# learning_zumo.net
KiCad netlist of a schematic drawn in EAGLE
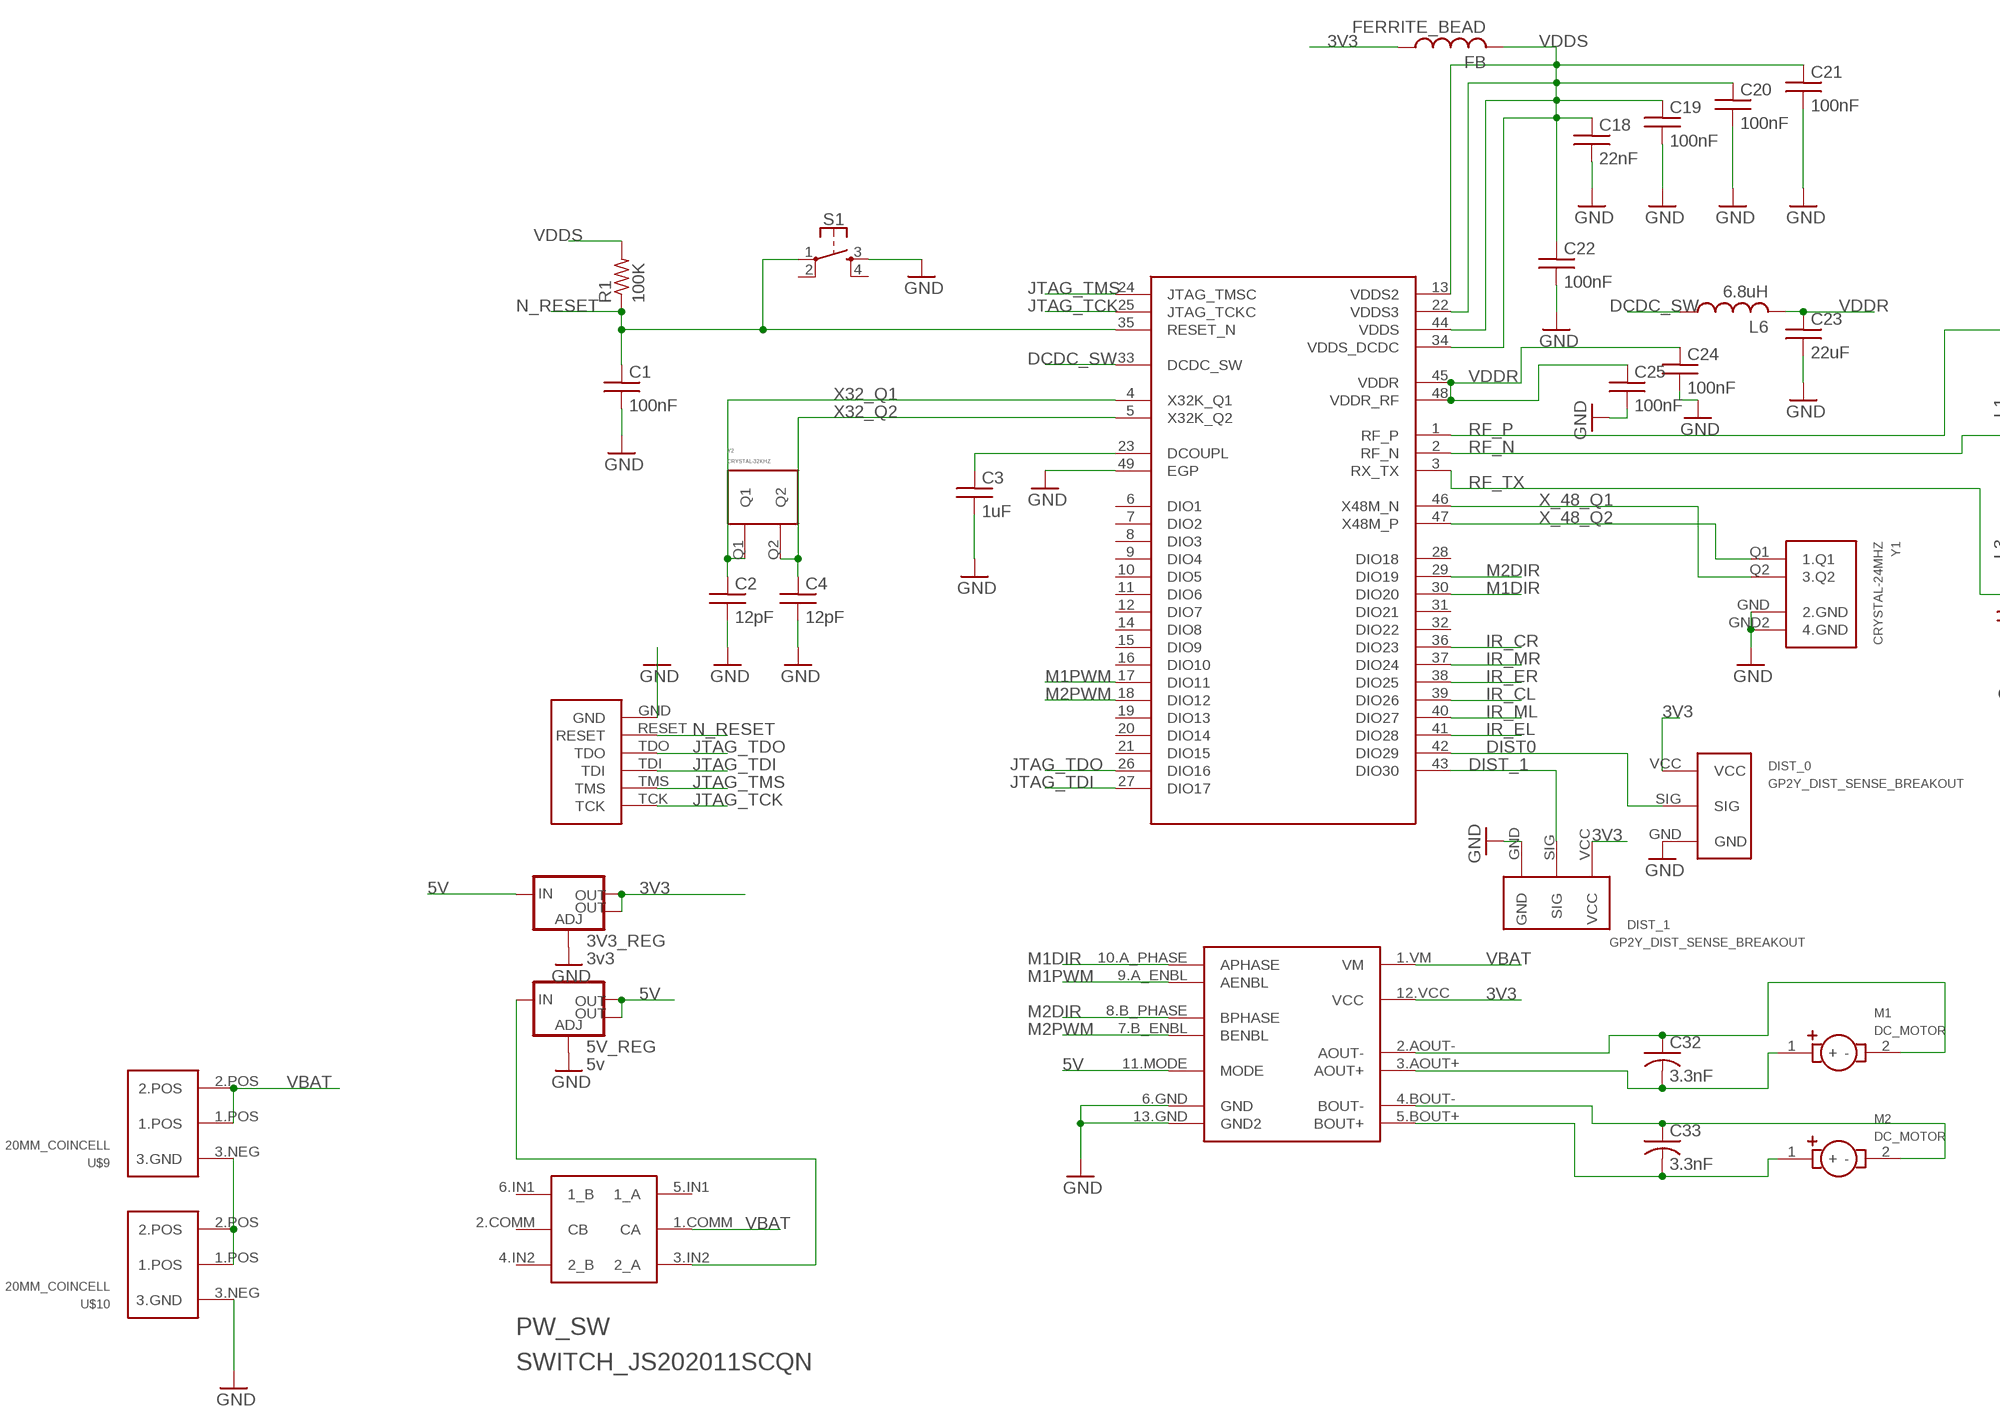
[diagram p0: schematic, sheet 1, part 1 of 2]
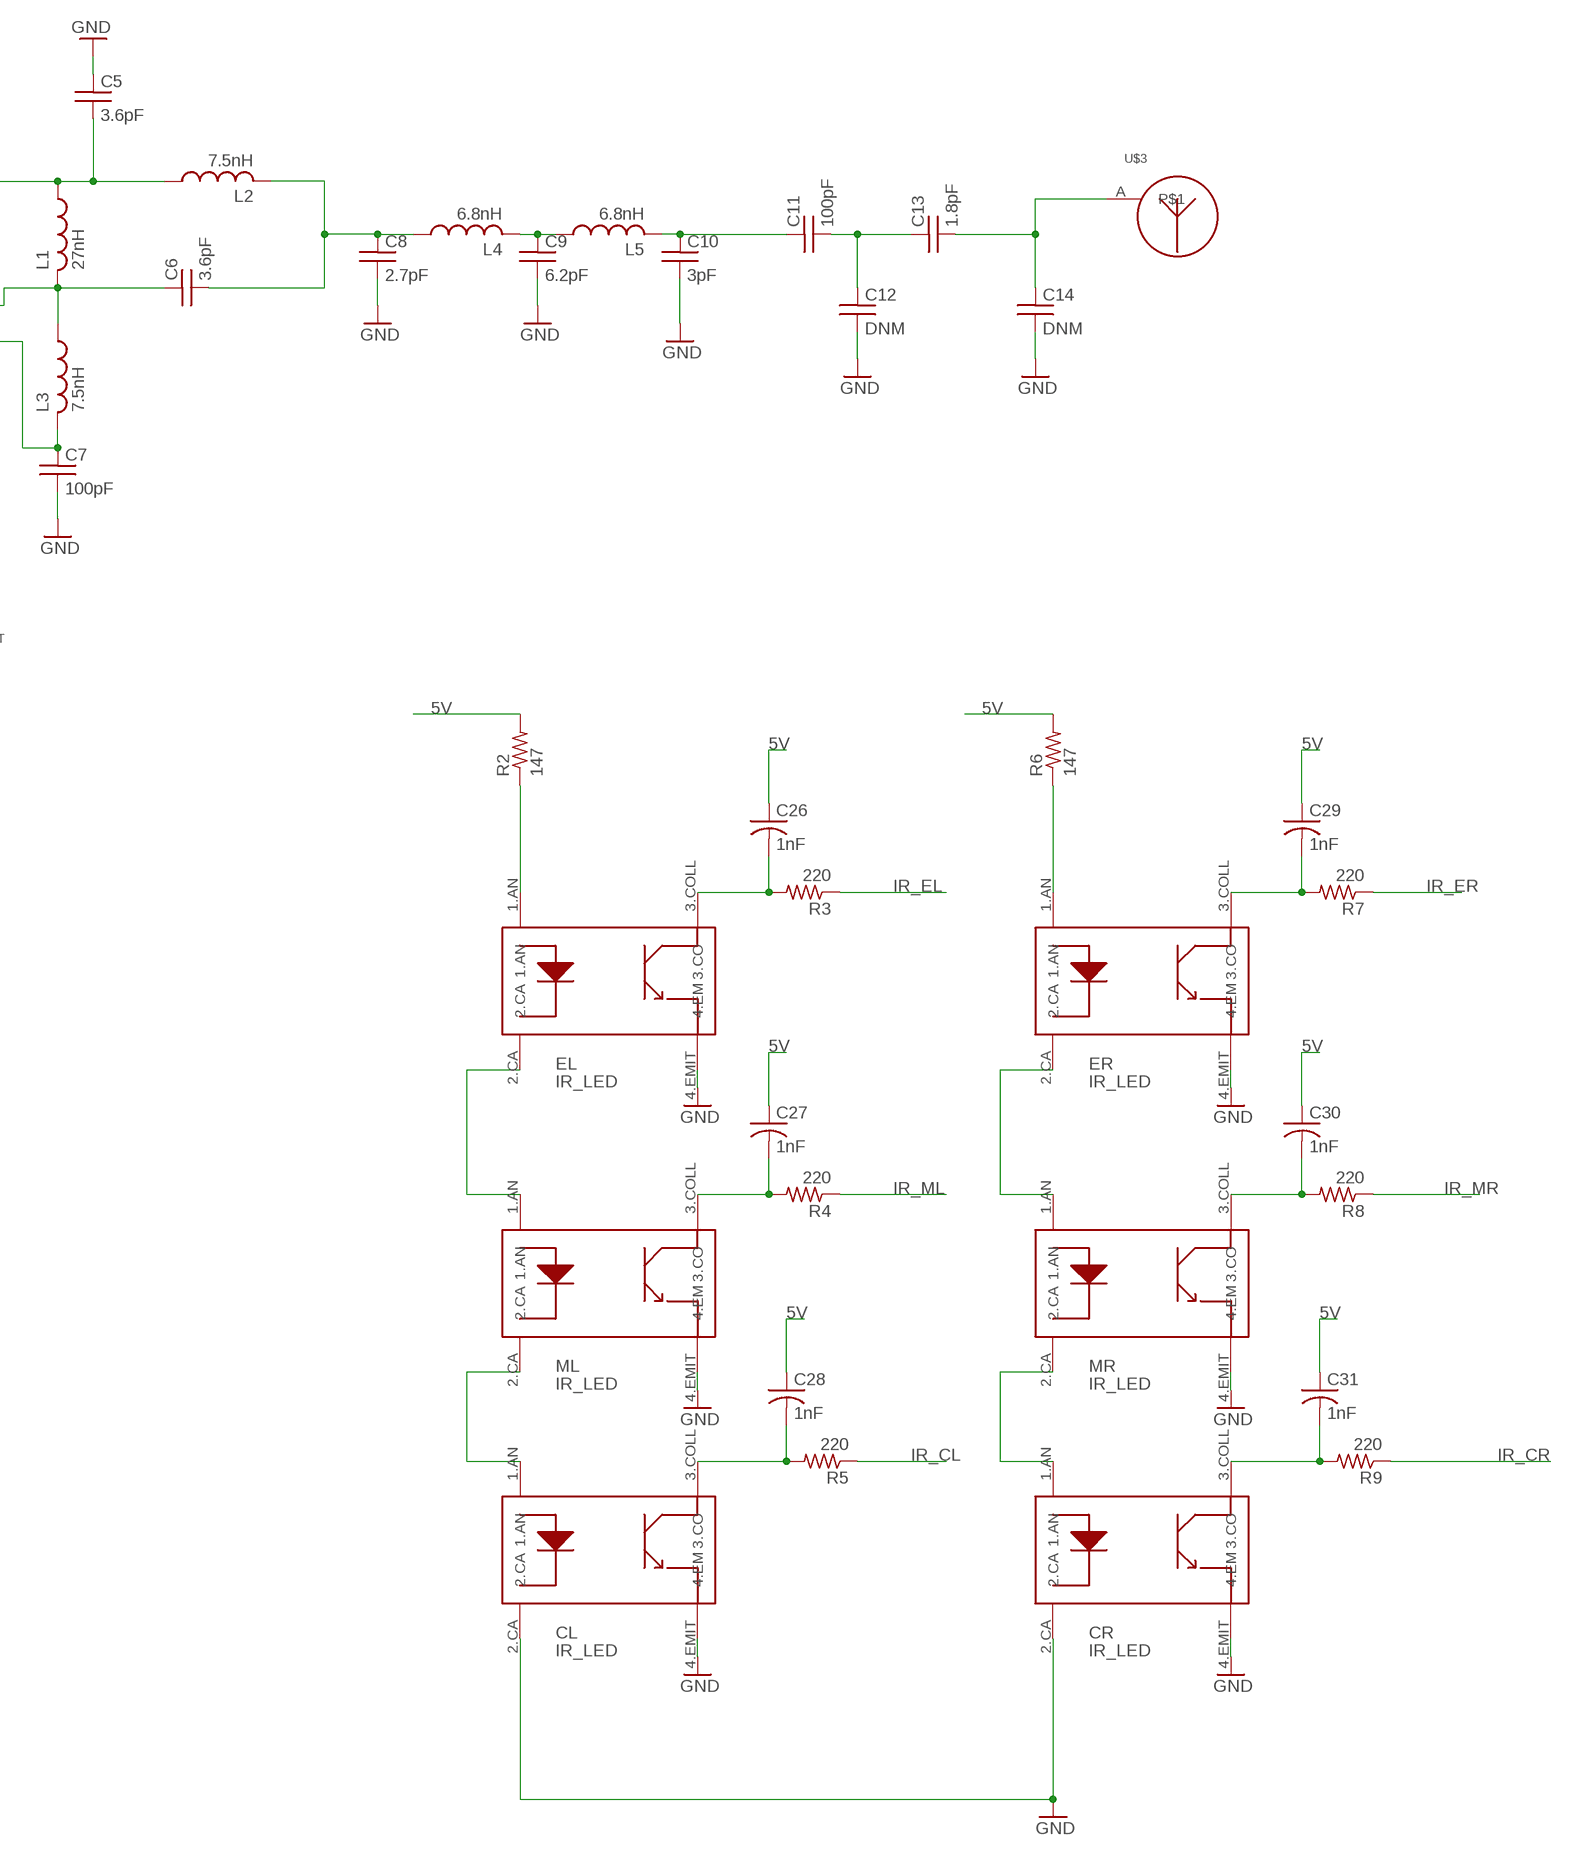
[diagram p1: schematic, sheet 1, part 2 of 2]

(export (version "E")
  (design (tool "Eeschema 10.0.6"))
  (components
    (comp (ref "3V3_REG")
      (value "3v3")
      (footprint "eagle-import:NU32V7_SOT223")
      (libsource (lib "eagle-import") (part "NU32V7_V_REG_LM1117SOT223"))
    )
    (comp (ref "5V_REG")
      (value "5v")
      (footprint "eagle-import:NU32V7_SOT223")
      (libsource (lib "eagle-import") (part "NU32V7_V_REG_LM1117SOT223"))
    )
    (comp (ref "C1")
      (value "100nF")
      (footprint "eagle-import:C0402_US")
      (libsource (lib "eagle-import") (part "C-US"))
    )
    (comp (ref "C2")
      (value "12pF")
      (footprint "eagle-import:C0402_US")
      (libsource (lib "eagle-import") (part "C-US"))
    )
    (comp (ref "C3")
      (value "1uF")
      (footprint "eagle-import:C0402_US")
      (libsource (lib "eagle-import") (part "C-US"))
    )
    (comp (ref "C4")
      (value "12pF")
      (footprint "eagle-import:C0402_US")
      (libsource (lib "eagle-import") (part "C-US"))
    )
    (comp (ref "C5")
      (value "3.6pF")
      (footprint "eagle-import:C0402_US")
      (libsource (lib "eagle-import") (part "C-US"))
    )
    (comp (ref "C6")
      (value "3.6pF")
      (footprint "eagle-import:C0402_US")
      (libsource (lib "eagle-import") (part "C-US"))
    )
    (comp (ref "C7")
      (value "100pF")
      (footprint "eagle-import:C0402_US")
      (libsource (lib "eagle-import") (part "C-US"))
    )
    (comp (ref "C8")
      (value "2.7pF")
      (footprint "eagle-import:C0402_US")
      (libsource (lib "eagle-import") (part "C-US"))
    )
    (comp (ref "C9")
      (value "6.2pF")
      (footprint "eagle-import:C0402_US")
      (libsource (lib "eagle-import") (part "C-US"))
    )
    (comp (ref "C10")
      (value "3pF")
      (footprint "eagle-import:C0402_US")
      (libsource (lib "eagle-import") (part "C-US"))
    )
    (comp (ref "C11")
      (value "100pF")
      (footprint "eagle-import:C0402_US")
      (libsource (lib "eagle-import") (part "C-US"))
    )
    (comp (ref "C12")
      (value "DNM")
      (footprint "eagle-import:C0402_US")
      (libsource (lib "eagle-import") (part "C-US"))
    )
    (comp (ref "C13")
      (value "1.8pF")
      (footprint "eagle-import:C0402_US")
      (libsource (lib "eagle-import") (part "C-US"))
    )
    (comp (ref "C14")
      (value "DNM")
      (footprint "eagle-import:C0402_US")
      (libsource (lib "eagle-import") (part "C-US"))
    )
    (comp (ref "C18")
      (value "22nF")
      (footprint "eagle-import:C0402_US")
      (libsource (lib "eagle-import") (part "C-US"))
    )
    (comp (ref "C19")
      (value "100nF")
      (footprint "eagle-import:C0402_US")
      (libsource (lib "eagle-import") (part "C-US"))
    )
    (comp (ref "C20")
      (value "100nF")
      (footprint "eagle-import:C0402_US")
      (libsource (lib "eagle-import") (part "C-US"))
    )
    (comp (ref "C21")
      (value "100nF")
      (footprint "eagle-import:C0402_US")
      (libsource (lib "eagle-import") (part "C-US"))
    )
    (comp (ref "C22")
      (value "100nF")
      (footprint "eagle-import:C0402_US")
      (libsource (lib "eagle-import") (part "C-US"))
    )
    (comp (ref "C23")
      (value "22uF")
      (footprint "eagle-import:C0402_US")
      (libsource (lib "eagle-import") (part "C-US"))
    )
    (comp (ref "C24")
      (value "100nF")
      (footprint "eagle-import:C0402_US")
      (libsource (lib "eagle-import") (part "C-US"))
    )
    (comp (ref "C25")
      (value "100nF")
      (footprint "eagle-import:C0402_US")
      (libsource (lib "eagle-import") (part "C-US"))
    )
    (comp (ref "C26")
      (value "1nF")
      (footprint "eagle-import:C0805")
      (libsource (lib "eagle-import") (part "C-USC0805"))
    )
    (comp (ref "C27")
      (value "1nF")
      (footprint "eagle-import:C0805")
      (libsource (lib "eagle-import") (part "C-USC0805"))
    )
    (comp (ref "C28")
      (value "1nF")
      (footprint "eagle-import:C0805")
      (libsource (lib "eagle-import") (part "C-USC0805"))
    )
    (comp (ref "C29")
      (value "1nF")
      (footprint "eagle-import:C0805")
      (libsource (lib "eagle-import") (part "C-USC0805"))
    )
    (comp (ref "C30")
      (value "1nF")
      (footprint "eagle-import:C0805")
      (libsource (lib "eagle-import") (part "C-USC0805"))
    )
    (comp (ref "C31")
      (value "1nF")
      (footprint "eagle-import:C0805")
      (libsource (lib "eagle-import") (part "C-USC0805"))
    )
    (comp (ref "C32")
      (value "3.3nF")
      (footprint "eagle-import:C0805")
      (libsource (lib "eagle-import") (part "C-USC0805"))
    )
    (comp (ref "C33")
      (value "3.3nF")
      (footprint "eagle-import:C0805")
      (libsource (lib "eagle-import") (part "C-USC0805"))
    )
    (comp (ref "CL")
      (value "IR_LED")
      (footprint "eagle-import:IR_LED")
      (libsource (lib "eagle-import") (part "IR_LED"))
    )
    (comp (ref "CR")
      (value "IR_LED")
      (footprint "eagle-import:IR_LED")
      (libsource (lib "eagle-import") (part "IR_LED"))
    )
    (comp (ref "DEBUG_HEADER")
      (value "DEBUG_BREAKOUT")
      (footprint "eagle-import:DEBUG_BREAKOUT")
      (libsource (lib "eagle-import") (part "DEBUG_BREAKOUT"))
    )
    (comp (ref "DIST_0")
      (value "GP2Y_DIST_SENSE_BREAKOUT")
      (footprint "eagle-import:1X03")
      (libsource (lib "eagle-import") (part "GP2Y_DIST_SENSE_BREAKOUT"))
    )
    (comp (ref "DIST_1")
      (value "GP2Y_DIST_SENSE_BREAKOUT")
      (footprint "eagle-import:1X03")
      (libsource (lib "eagle-import") (part "GP2Y_DIST_SENSE_BREAKOUT"))
    )
    (comp (ref "DRV8835")
      (value "DRV8835DRV8835")
      (footprint "eagle-import:DRV8835")
      (libsource (lib "eagle-import") (part "DRV8835DRV8835"))
    )
    (comp (ref "EL")
      (value "IR_LED")
      (footprint "eagle-import:IR_LED")
      (libsource (lib "eagle-import") (part "IR_LED"))
    )
    (comp (ref "ER")
      (value "IR_LED")
      (footprint "eagle-import:IR_LED")
      (libsource (lib "eagle-import") (part "IR_LED"))
    )
    (comp (ref "FB")
      (value "FERRITE_BEAD")
      (footprint "eagle-import:FERRITE_BEAD")
      (libsource (lib "eagle-import") (part "FERRITE_BEAD"))
    )
    (comp (ref "L1")
      (value "27nH")
      (footprint "eagle-import:L0402_US")
      (libsource (lib "eagle-import") (part "L-US"))
    )
    (comp (ref "L2")
      (value "7.5nH")
      (footprint "eagle-import:L0402_US")
      (libsource (lib "eagle-import") (part "L-US"))
    )
    (comp (ref "L3")
      (value "7.5nH")
      (footprint "eagle-import:L0402_US")
      (libsource (lib "eagle-import") (part "L-US"))
    )
    (comp (ref "L4")
      (value "6.8nH")
      (footprint "eagle-import:L0402_US")
      (libsource (lib "eagle-import") (part "L-US"))
    )
    (comp (ref "L5")
      (value "6.8nH")
      (footprint "eagle-import:L0402_US")
      (libsource (lib "eagle-import") (part "L-US"))
    )
    (comp (ref "L6")
      (value "6.8uH")
      (footprint "eagle-import:R0805")
      (libsource (lib "eagle-import") (part "L-USL0805"))
    )
    (comp (ref "M1")
      (value "DC_MOTOR")
      (footprint "eagle-import:1X02")
      (libsource (lib "eagle-import") (part "DC_MOTOR"))
    )
    (comp (ref "M2")
      (value "DC_MOTOR")
      (footprint "eagle-import:1X02")
      (libsource (lib "eagle-import") (part "DC_MOTOR"))
    )
    (comp (ref "ML")
      (value "IR_LED")
      (footprint "eagle-import:IR_LED")
      (libsource (lib "eagle-import") (part "IR_LED"))
    )
    (comp (ref "MR")
      (value "IR_LED")
      (footprint "eagle-import:IR_LED")
      (libsource (lib "eagle-import") (part "IR_LED"))
    )
    (comp (ref "PW_SW")
      (value "SWITCH_JS202011SCQN")
      (footprint "eagle-import:SWITCH_JS202011SCQN")
      (libsource (lib "eagle-import") (part "SWITCH_JS202011SCQN"))
    )
    (comp (ref "R1")
      (value "100K")
      (footprint "eagle-import:R0402_US")
      (libsource (lib "eagle-import") (part "R-US{dblquote}"))
    )
    (comp (ref "R2")
      (value "147")
      (footprint "eagle-import:R0805")
      (libsource (lib "eagle-import") (part "R-US_R0805"))
    )
    (comp (ref "R3")
      (value "220")
      (footprint "eagle-import:R0805")
      (libsource (lib "eagle-import") (part "R-US_R0805"))
    )
    (comp (ref "R4")
      (value "220")
      (footprint "eagle-import:R0805")
      (libsource (lib "eagle-import") (part "R-US_R0805"))
    )
    (comp (ref "R5")
      (value "220")
      (footprint "eagle-import:R0805")
      (libsource (lib "eagle-import") (part "R-US_R0805"))
    )
    (comp (ref "R6")
      (value "147")
      (footprint "eagle-import:R0805")
      (libsource (lib "eagle-import") (part "R-US_R0805"))
    )
    (comp (ref "R7")
      (value "220")
      (footprint "eagle-import:R0805")
      (libsource (lib "eagle-import") (part "R-US_R0805"))
    )
    (comp (ref "R8")
      (value "220")
      (footprint "eagle-import:R0805")
      (libsource (lib "eagle-import") (part "R-US_R0805"))
    )
    (comp (ref "R9")
      (value "220")
      (footprint "eagle-import:R0805")
      (libsource (lib "eagle-import") (part "R-US_R0805"))
    )
    (comp (ref "S1")
      (value "MOMENTARY-SWITCH-SPST-2-SMD-4.6X2.8MM")
      (footprint "eagle-import:TACTILE_SWITCH_SMD_4.6X2.8MM")
      (libsource (lib "eagle-import") (part "MOMENTARY-SWITCH-SPST-2-SMD-4.6X2.8MM"))
    )
    (comp (ref "U$1")
      (value "CC1310")
      (footprint "eagle-import:QFN50P700X700X100-49N")
      (libsource (lib "eagle-import") (part "CC1310"))
    )
    (comp (ref "U$3")
      (value "ANTENNA")
      (footprint "eagle-import:ANTENNA")
      (libsource (lib "eagle-import") (part "ANTENNA"))
    )
    (comp (ref "U$9")
      (value "20MM_COINCELL")
      (footprint "eagle-import:20MM_COINCELL")
      (libsource (lib "eagle-import") (part "20MM_COINCELL"))
    )
    (comp (ref "U$10")
      (value "20MM_COINCELL")
      (footprint "eagle-import:20MM_COINCELL")
      (libsource (lib "eagle-import") (part "20MM_COINCELL"))
    )
    (comp (ref "Y1")
      (value "CRYSTAL-24MHZ")
      (footprint "eagle-import:CRYSTAL-24MHZ")
      (libsource (lib "eagle-import") (part "CRYSTAL-24MHZ"))
    )
    (comp (ref "Y2")
      (value "CRYSTAL-32KHZ")
      (footprint "eagle-import:CRYSTAL-32KHZ")
      (libsource (lib "eagle-import") (part "CRYSTAL-32KHZ"))
    )
  )
  (nets
    (net (code "1") (name "/3V3") (class "Default")
      (node (ref "3V3_REG") (pin "OUTPUT") (pinfunction "OUT_OUTPUT") (pintype "output"))
      (node (ref "3V3_REG") (pin "VOUT") (pinfunction "OUT_VOUT") (pintype "output"))
      (node (ref "DIST_0") (pin "VCC") (pinfunction "VCC_VCC") (pintype "bidirectional"))
      (node (ref "DIST_1") (pin "VCC") (pinfunction "VCC_VCC") (pintype "bidirectional"))
      (node (ref "DRV8835") (pin "12.VCC") (pinfunction "VCC_12.VCC") (pintype "bidirectional"))
      (node (ref "FB") (pin "P$1") (pinfunction "1_P$1") (pintype "passive"))
    )
    (net (code "2") (name "/5V") (class "Default")
      (node (ref "3V3_REG") (pin "INPUT") (pinfunction "IN_INPUT") (pintype "input"))
      (node (ref "5V_REG") (pin "OUTPUT") (pinfunction "OUT_OUTPUT") (pintype "output"))
      (node (ref "5V_REG") (pin "VOUT") (pinfunction "OUT_VOUT") (pintype "output"))
      (node (ref "C26") (pin "1") (pinfunction "1_1") (pintype "passive"))
      (node (ref "C27") (pin "1") (pinfunction "1_1") (pintype "passive"))
      (node (ref "C28") (pin "1") (pinfunction "1_1") (pintype "passive"))
      (node (ref "C29") (pin "1") (pinfunction "1_1") (pintype "passive"))
      (node (ref "C30") (pin "1") (pinfunction "1_1") (pintype "passive"))
      (node (ref "C31") (pin "1") (pinfunction "1_1") (pintype "passive"))
      (node (ref "DRV8835") (pin "11.MODE") (pinfunction "MODE_11.MODE") (pintype "bidirectional"))
      (node (ref "R2") (pin "2") (pinfunction "2_2") (pintype "passive"))
      (node (ref "R6") (pin "2") (pinfunction "2_2") (pintype "passive"))
    )
    (net (code "3") (name "/DCDC_SW") (class "Default")
      (node (ref "L6") (pin "1") (pinfunction "1_1") (pintype "passive"))
      (node (ref "U$1") (pin "33") (pinfunction "DCDC_SW_33") (pintype "bidirectional"))
    )
    (net (code "4") (name "/DIST0") (class "Default")
      (node (ref "DIST_0") (pin "SIG") (pinfunction "SIG_SIG") (pintype "bidirectional"))
      (node (ref "U$1") (pin "42") (pinfunction "DIO29_42") (pintype "bidirectional"))
    )
    (net (code "5") (name "/DIST_1") (class "Default")
      (node (ref "DIST_1") (pin "SIG") (pinfunction "SIG_SIG") (pintype "bidirectional"))
      (node (ref "U$1") (pin "43") (pinfunction "DIO30_43") (pintype "bidirectional"))
    )
    (net (code "6") (name "/IR_CL") (class "Default")
      (node (ref "R5") (pin "1") (pinfunction "1_1") (pintype "passive"))
      (node (ref "U$1") (pin "39") (pinfunction "DIO26_39") (pintype "bidirectional"))
    )
    (net (code "7") (name "/IR_CR") (class "Default")
      (node (ref "R9") (pin "1") (pinfunction "1_1") (pintype "passive"))
      (node (ref "U$1") (pin "36") (pinfunction "DIO23_36") (pintype "bidirectional"))
    )
    (net (code "8") (name "/IR_EL") (class "Default")
      (node (ref "R3") (pin "1") (pinfunction "1_1") (pintype "passive"))
      (node (ref "U$1") (pin "41") (pinfunction "DIO28_41") (pintype "bidirectional"))
    )
    (net (code "9") (name "/IR_ER") (class "Default")
      (node (ref "R7") (pin "1") (pinfunction "1_1") (pintype "passive"))
      (node (ref "U$1") (pin "38") (pinfunction "DIO25_38") (pintype "bidirectional"))
    )
    (net (code "10") (name "/IR_ML") (class "Default")
      (node (ref "R4") (pin "1") (pinfunction "1_1") (pintype "passive"))
      (node (ref "U$1") (pin "40") (pinfunction "DIO27_40") (pintype "bidirectional"))
    )
    (net (code "11") (name "/IR_MR") (class "Default")
      (node (ref "R8") (pin "1") (pinfunction "1_1") (pintype "passive"))
      (node (ref "U$1") (pin "37") (pinfunction "DIO24_37") (pintype "bidirectional"))
    )
    (net (code "12") (name "/JTAG_TCK") (class "Default")
      (node (ref "DEBUG_HEADER") (pin "TCK") (pinfunction "TCK_TCK") (pintype "bidirectional"))
      (node (ref "U$1") (pin "25") (pinfunction "JTAG_TCKC_25") (pintype "bidirectional"))
    )
    (net (code "13") (name "/JTAG_TDI") (class "Default")
      (node (ref "DEBUG_HEADER") (pin "TDI") (pinfunction "TDI_TDI") (pintype "bidirectional"))
      (node (ref "U$1") (pin "27") (pinfunction "DIO17_27") (pintype "bidirectional"))
    )
    (net (code "14") (name "/JTAG_TDO") (class "Default")
      (node (ref "DEBUG_HEADER") (pin "TDO") (pinfunction "TDO_TDO") (pintype "bidirectional"))
      (node (ref "U$1") (pin "26") (pinfunction "DIO16_26") (pintype "bidirectional"))
    )
    (net (code "15") (name "/JTAG_TMS") (class "Default")
      (node (ref "DEBUG_HEADER") (pin "TMS") (pinfunction "TMS_TMS") (pintype "bidirectional"))
      (node (ref "U$1") (pin "24") (pinfunction "JTAG_TMSC_24") (pintype "bidirectional"))
    )
    (net (code "16") (name "/M1DIR") (class "Default")
      (node (ref "DRV8835") (pin "10.A_PHASE") (pinfunction "APHASE_10.A_PHASE") (pintype "bidirectional"))
      (node (ref "U$1") (pin "30") (pinfunction "DIO20_30") (pintype "bidirectional"))
    )
    (net (code "17") (name "/M1PWM") (class "Default")
      (node (ref "DRV8835") (pin "9.A_ENBL") (pinfunction "AENBL_9.A_ENBL") (pintype "bidirectional"))
      (node (ref "U$1") (pin "17") (pinfunction "DIO11_17") (pintype "bidirectional"))
    )
    (net (code "18") (name "/M2DIR") (class "Default")
      (node (ref "DRV8835") (pin "8.B_PHASE") (pinfunction "BPHASE_8.B_PHASE") (pintype "bidirectional"))
      (node (ref "U$1") (pin "29") (pinfunction "DIO19_29") (pintype "bidirectional"))
    )
    (net (code "19") (name "/M2PWM") (class "Default")
      (node (ref "DRV8835") (pin "7.B_ENBL") (pinfunction "BENBL_7.B_ENBL") (pintype "bidirectional"))
      (node (ref "U$1") (pin "18") (pinfunction "DIO12_18") (pintype "bidirectional"))
    )
    (net (code "20") (name "/N_RESET") (class "Default")
      (node (ref "C1") (pin "1") (pinfunction "P$1_1") (pintype "passive"))
      (node (ref "DEBUG_HEADER") (pin "RESET") (pinfunction "RESET_RESET") (pintype "bidirectional"))
      (node (ref "R1") (pin "P$1") (pinfunction "1_P$1") (pintype "passive"))
      (node (ref "S1") (pin "1") (pinfunction "1_1") (pintype "passive"))
      (node (ref "U$1") (pin "35") (pinfunction "RESET_N_35") (pintype "bidirectional"))
    )
    (net (code "21") (name "/RF_N") (class "Default")
      (node (ref "C6") (pin "1") (pinfunction "P$1_1") (pintype "passive"))
      (node (ref "L1") (pin "P$2") (pinfunction "2_P$2") (pintype "passive"))
      (node (ref "L3") (pin "P$1") (pinfunction "1_P$1") (pintype "passive"))
      (node (ref "U$1") (pin "2") (pinfunction "RF_N_2") (pintype "bidirectional"))
    )
    (net (code "22") (name "/RF_P") (class "Default")
      (node (ref "C5") (pin "2") (pinfunction "P$2_2") (pintype "passive"))
      (node (ref "L1") (pin "P$1") (pinfunction "1_P$1") (pintype "passive"))
      (node (ref "L2") (pin "P$1") (pinfunction "1_P$1") (pintype "passive"))
      (node (ref "U$1") (pin "1") (pinfunction "RF_P_1") (pintype "bidirectional"))
    )
    (net (code "23") (name "/RF_TX") (class "Default")
      (node (ref "C7") (pin "1") (pinfunction "P$1_1") (pintype "passive"))
      (node (ref "L3") (pin "P$2") (pinfunction "2_P$2") (pintype "passive"))
      (node (ref "U$1") (pin "3") (pinfunction "RX_TX_3") (pintype "bidirectional"))
    )
    (net (code "24") (name "/VBAT") (class "Default")
      (node (ref "DRV8835") (pin "1.VM") (pinfunction "VM_1.VM") (pintype "bidirectional"))
      (node (ref "PW_SW") (pin "1.COMM") (pinfunction "CA_1.COMM") (pintype "bidirectional"))
      (node (ref "U$9") (pin "1.POS") (pinfunction "1.POS_1.POS") (pintype "bidirectional"))
      (node (ref "U$9") (pin "2.POS") (pinfunction "2.POS_2.POS") (pintype "bidirectional"))
    )
    (net (code "25") (name "/VDDR") (class "Default")
      (node (ref "C23") (pin "1") (pinfunction "P$1_1") (pintype "passive"))
      (node (ref "C24") (pin "1") (pinfunction "P$1_1") (pintype "passive"))
      (node (ref "C25") (pin "1") (pinfunction "P$1_1") (pintype "passive"))
      (node (ref "L6") (pin "2") (pinfunction "2_2") (pintype "passive"))
      (node (ref "U$1") (pin "45") (pinfunction "VDDR_45") (pintype "bidirectional"))
      (node (ref "U$1") (pin "48") (pinfunction "VDDR_RF_48") (pintype "bidirectional"))
    )
    (net (code "26") (name "/VDDS") (class "Default")
      (node (ref "C18") (pin "1") (pinfunction "P$1_1") (pintype "passive"))
      (node (ref "C19") (pin "1") (pinfunction "P$1_1") (pintype "passive"))
      (node (ref "C20") (pin "1") (pinfunction "P$1_1") (pintype "passive"))
      (node (ref "C21") (pin "1") (pinfunction "P$1_1") (pintype "passive"))
      (node (ref "C22") (pin "1") (pinfunction "P$1_1") (pintype "passive"))
      (node (ref "FB") (pin "P$2") (pinfunction "2_P$2") (pintype "passive"))
      (node (ref "R1") (pin "P$2") (pinfunction "2_P$2") (pintype "passive"))
      (node (ref "U$1") (pin "13") (pinfunction "VDDS2_13") (pintype "bidirectional"))
      (node (ref "U$1") (pin "22") (pinfunction "VDDS3_22") (pintype "bidirectional"))
      (node (ref "U$1") (pin "34") (pinfunction "VDDS_DCDC_34") (pintype "bidirectional"))
      (node (ref "U$1") (pin "44") (pinfunction "VDDS_44") (pintype "bidirectional"))
    )
    (net (code "27") (name "/X32_Q1") (class "Default")
      (node (ref "C2") (pin "1") (pinfunction "P$1_1") (pintype "passive"))
      (node (ref "U$1") (pin "4") (pinfunction "X32K_Q1_4") (pintype "bidirectional"))
      (node (ref "Y2") (pin "Q1") (pinfunction "Q1_Q1") (pintype "bidirectional"))
    )
    (net (code "28") (name "/X32_Q2") (class "Default")
      (node (ref "C4") (pin "1") (pinfunction "P$1_1") (pintype "passive"))
      (node (ref "U$1") (pin "5") (pinfunction "X32K_Q2_5") (pintype "bidirectional"))
      (node (ref "Y2") (pin "Q2") (pinfunction "Q2_Q2") (pintype "bidirectional"))
    )
    (net (code "29") (name "/X_48_Q1") (class "Default")
      (node (ref "U$1") (pin "46") (pinfunction "X48M_N_46") (pintype "bidirectional"))
      (node (ref "Y1") (pin "Q2") (pinfunction "3.Q2_Q2") (pintype "bidirectional"))
    )
    (net (code "30") (name "/X_48_Q2") (class "Default")
      (node (ref "U$1") (pin "47") (pinfunction "X48M_P_47") (pintype "bidirectional"))
      (node (ref "Y1") (pin "Q1") (pinfunction "1.Q1_Q1") (pintype "bidirectional"))
    )
    (net (code "31") (name "GND") (class "Default")
      (node (ref "3V3_REG") (pin "GND") (pinfunction "ADJ_GND") (pintype "input"))
      (node (ref "5V_REG") (pin "GND") (pinfunction "ADJ_GND") (pintype "input"))
      (node (ref "C1") (pin "2") (pinfunction "P$2_2") (pintype "passive"))
      (node (ref "C10") (pin "2") (pinfunction "P$2_2") (pintype "passive"))
      (node (ref "C12") (pin "2") (pinfunction "P$2_2") (pintype "passive"))
      (node (ref "C14") (pin "2") (pinfunction "P$2_2") (pintype "passive"))
      (node (ref "C18") (pin "2") (pinfunction "P$2_2") (pintype "passive"))
      (node (ref "C19") (pin "2") (pinfunction "P$2_2") (pintype "passive"))
      (node (ref "C2") (pin "2") (pinfunction "P$2_2") (pintype "passive"))
      (node (ref "C20") (pin "2") (pinfunction "P$2_2") (pintype "passive"))
      (node (ref "C21") (pin "2") (pinfunction "P$2_2") (pintype "passive"))
      (node (ref "C22") (pin "2") (pinfunction "P$2_2") (pintype "passive"))
      (node (ref "C23") (pin "2") (pinfunction "P$2_2") (pintype "passive"))
      (node (ref "C24") (pin "2") (pinfunction "P$2_2") (pintype "passive"))
      (node (ref "C25") (pin "2") (pinfunction "P$2_2") (pintype "passive"))
      (node (ref "C3") (pin "2") (pinfunction "P$2_2") (pintype "passive"))
      (node (ref "C4") (pin "2") (pinfunction "P$2_2") (pintype "passive"))
      (node (ref "C5") (pin "1") (pinfunction "P$1_1") (pintype "passive"))
      (node (ref "C7") (pin "2") (pinfunction "P$2_2") (pintype "passive"))
      (node (ref "C8") (pin "2") (pinfunction "P$2_2") (pintype "passive"))
      (node (ref "C9") (pin "2") (pinfunction "P$2_2") (pintype "passive"))
      (node (ref "CL") (pin "2.CA") (pinfunction "2.CA_2.CA") (pintype "bidirectional"))
      (node (ref "CL") (pin "4.EMIT") (pinfunction "4.EM_4.EMIT") (pintype "bidirectional"))
      (node (ref "CR") (pin "2.CA") (pinfunction "2.CA_2.CA") (pintype "bidirectional"))
      (node (ref "CR") (pin "4.EMIT") (pinfunction "4.EM_4.EMIT") (pintype "bidirectional"))
      (node (ref "DEBUG_HEADER") (pin "GND") (pinfunction "GND_GND") (pintype "bidirectional"))
      (node (ref "DIST_0") (pin "GND") (pinfunction "GND_GND") (pintype "bidirectional"))
      (node (ref "DIST_1") (pin "GND") (pinfunction "GND_GND") (pintype "bidirectional"))
      (node (ref "DRV8835") (pin "13.GND") (pinfunction "GND2_13.GND") (pintype "bidirectional"))
      (node (ref "DRV8835") (pin "6.GND") (pinfunction "GND_6.GND") (pintype "bidirectional"))
      (node (ref "EL") (pin "4.EMIT") (pinfunction "4.EM_4.EMIT") (pintype "bidirectional"))
      (node (ref "ER") (pin "4.EMIT") (pinfunction "4.EM_4.EMIT") (pintype "bidirectional"))
      (node (ref "ML") (pin "4.EMIT") (pinfunction "4.EM_4.EMIT") (pintype "bidirectional"))
      (node (ref "MR") (pin "4.EMIT") (pinfunction "4.EM_4.EMIT") (pintype "bidirectional"))
      (node (ref "S1") (pin "3") (pinfunction "3_3") (pintype "passive"))
      (node (ref "U$1") (pin "49") (pinfunction "EGP_49") (pintype "bidirectional"))
      (node (ref "U$10") (pin "3.NEG") (pinfunction "3.GND_3.NEG") (pintype "bidirectional"))
      (node (ref "Y1") (pin "GND") (pinfunction "2.GND_GND") (pintype "bidirectional"))
      (node (ref "Y1") (pin "GND2") (pinfunction "4.GND_GND2") (pintype "bidirectional"))
    )
    (net (code "32") (name "Net-(5V_REG-IN)") (class "Default")
      (node (ref "5V_REG") (pin "INPUT") (pinfunction "IN_INPUT") (pintype "input"))
      (node (ref "PW_SW") (pin "3.IN2") (pinfunction "2_A_3.IN2") (pintype "bidirectional"))
    )
    (net (code "33") (name "Net-(C3-P$1)") (class "Default")
      (node (ref "C3") (pin "1") (pinfunction "P$1_1") (pintype "passive"))
      (node (ref "U$1") (pin "23") (pinfunction "DCOUPL_23") (pintype "bidirectional"))
    )
    (net (code "34") (name "Net-(C6-P$2)") (class "Default")
      (node (ref "C6") (pin "2") (pinfunction "P$2_2") (pintype "passive"))
      (node (ref "C8") (pin "1") (pinfunction "P$1_1") (pintype "passive"))
      (node (ref "L2") (pin "P$2") (pinfunction "2_P$2") (pintype "passive"))
      (node (ref "L4") (pin "P$1") (pinfunction "1_P$1") (pintype "passive"))
    )
    (net (code "35") (name "Net-(C9-P$1)") (class "Default")
      (node (ref "C9") (pin "1") (pinfunction "P$1_1") (pintype "passive"))
      (node (ref "L4") (pin "P$2") (pinfunction "2_P$2") (pintype "passive"))
      (node (ref "L5") (pin "P$1") (pinfunction "1_P$1") (pintype "passive"))
    )
    (net (code "36") (name "Net-(C10-P$1)") (class "Default")
      (node (ref "C10") (pin "1") (pinfunction "P$1_1") (pintype "passive"))
      (node (ref "C11") (pin "1") (pinfunction "P$1_1") (pintype "passive"))
      (node (ref "L5") (pin "P$2") (pinfunction "2_P$2") (pintype "passive"))
    )
    (net (code "37") (name "Net-(C11-P$2)") (class "Default")
      (node (ref "C11") (pin "2") (pinfunction "P$2_2") (pintype "passive"))
      (node (ref "C12") (pin "1") (pinfunction "P$1_1") (pintype "passive"))
      (node (ref "C13") (pin "1") (pinfunction "P$1_1") (pintype "passive"))
    )
    (net (code "38") (name "Net-(C13-P$2)") (class "Default")
      (node (ref "C13") (pin "2") (pinfunction "P$2_2") (pintype "passive"))
      (node (ref "C14") (pin "1") (pinfunction "P$1_1") (pintype "passive"))
      (node (ref "U$3") (pin "A") (pinfunction "P$1_A") (pintype "bidirectional"))
    )
    (net (code "39") (name "Net-(CL-3.CO)") (class "Default")
      (node (ref "C28") (pin "2") (pinfunction "2_2") (pintype "passive"))
      (node (ref "CL") (pin "3.COLL") (pinfunction "3.CO_3.COLL") (pintype "bidirectional"))
      (node (ref "R5") (pin "2") (pinfunction "2_2") (pintype "passive"))
    )
    (net (code "40") (name "Net-(CL-Pad1.AN)") (class "Default")
      (node (ref "CL") (pin "1.AN") (pinfunction "1.AN_1.AN") (pintype "bidirectional"))
      (node (ref "ML") (pin "2.CA") (pinfunction "2.CA_2.CA") (pintype "bidirectional"))
    )
    (net (code "41") (name "Net-(CR-3.CO)") (class "Default")
      (node (ref "C31") (pin "2") (pinfunction "2_2") (pintype "passive"))
      (node (ref "CR") (pin "3.COLL") (pinfunction "3.CO_3.COLL") (pintype "bidirectional"))
      (node (ref "R9") (pin "2") (pinfunction "2_2") (pintype "passive"))
    )
    (net (code "42") (name "Net-(CR-Pad1.AN)") (class "Default")
      (node (ref "CR") (pin "1.AN") (pinfunction "1.AN_1.AN") (pintype "bidirectional"))
      (node (ref "MR") (pin "2.CA") (pinfunction "2.CA_2.CA") (pintype "bidirectional"))
    )
    (net (code "43") (name "Net-(DRV8835-AOUT+)") (class "Default")
      (node (ref "C32") (pin "2") (pinfunction "2_2") (pintype "passive"))
      (node (ref "DRV8835") (pin "3.AOUT+") (pinfunction "AOUT+_3.AOUT+") (pintype "bidirectional"))
      (node (ref "M1") (pin "1") (pinfunction "+_1") (pintype "bidirectional"))
    )
    (net (code "44") (name "Net-(DRV8835-AOUT-)") (class "Default")
      (node (ref "C32") (pin "1") (pinfunction "1_1") (pintype "passive"))
      (node (ref "DRV8835") (pin "2.AOUT-") (pinfunction "AOUT-_2.AOUT-") (pintype "bidirectional"))
      (node (ref "M1") (pin "2") (pinfunction "-_2") (pintype "bidirectional"))
    )
    (net (code "45") (name "Net-(DRV8835-BOUT+)") (class "Default")
      (node (ref "C33") (pin "2") (pinfunction "2_2") (pintype "passive"))
      (node (ref "DRV8835") (pin "5.BOUT+") (pinfunction "BOUT+_5.BOUT+") (pintype "bidirectional"))
      (node (ref "M2") (pin "1") (pinfunction "+_1") (pintype "bidirectional"))
    )
    (net (code "46") (name "Net-(DRV8835-BOUT-)") (class "Default")
      (node (ref "C33") (pin "1") (pinfunction "1_1") (pintype "passive"))
      (node (ref "DRV8835") (pin "4.BOUT-") (pinfunction "BOUT-_4.BOUT-") (pintype "bidirectional"))
      (node (ref "M2") (pin "2") (pinfunction "-_2") (pintype "bidirectional"))
    )
    (net (code "47") (name "Net-(EL-3.CO)") (class "Default")
      (node (ref "C26") (pin "2") (pinfunction "2_2") (pintype "passive"))
      (node (ref "EL") (pin "3.COLL") (pinfunction "3.CO_3.COLL") (pintype "bidirectional"))
      (node (ref "R3") (pin "2") (pinfunction "2_2") (pintype "passive"))
    )
    (net (code "48") (name "Net-(EL-Pad1.AN)") (class "Default")
      (node (ref "EL") (pin "1.AN") (pinfunction "1.AN_1.AN") (pintype "bidirectional"))
      (node (ref "R2") (pin "1") (pinfunction "1_1") (pintype "passive"))
    )
    (net (code "49") (name "Net-(EL-Pad2.CA)") (class "Default")
      (node (ref "EL") (pin "2.CA") (pinfunction "2.CA_2.CA") (pintype "bidirectional"))
      (node (ref "ML") (pin "1.AN") (pinfunction "1.AN_1.AN") (pintype "bidirectional"))
    )
    (net (code "50") (name "Net-(ER-3.CO)") (class "Default")
      (node (ref "C29") (pin "2") (pinfunction "2_2") (pintype "passive"))
      (node (ref "ER") (pin "3.COLL") (pinfunction "3.CO_3.COLL") (pintype "bidirectional"))
      (node (ref "R7") (pin "2") (pinfunction "2_2") (pintype "passive"))
    )
    (net (code "51") (name "Net-(ER-Pad1.AN)") (class "Default")
      (node (ref "ER") (pin "1.AN") (pinfunction "1.AN_1.AN") (pintype "bidirectional"))
      (node (ref "R6") (pin "1") (pinfunction "1_1") (pintype "passive"))
    )
    (net (code "52") (name "Net-(ER-Pad2.CA)") (class "Default")
      (node (ref "ER") (pin "2.CA") (pinfunction "2.CA_2.CA") (pintype "bidirectional"))
      (node (ref "MR") (pin "1.AN") (pinfunction "1.AN_1.AN") (pintype "bidirectional"))
    )
    (net (code "53") (name "Net-(ML-3.CO)") (class "Default")
      (node (ref "C27") (pin "2") (pinfunction "2_2") (pintype "passive"))
      (node (ref "ML") (pin "3.COLL") (pinfunction "3.CO_3.COLL") (pintype "bidirectional"))
      (node (ref "R4") (pin "2") (pinfunction "2_2") (pintype "passive"))
    )
    (net (code "54") (name "Net-(MR-3.CO)") (class "Default")
      (node (ref "C30") (pin "2") (pinfunction "2_2") (pintype "passive"))
      (node (ref "MR") (pin "3.COLL") (pinfunction "3.CO_3.COLL") (pintype "bidirectional"))
      (node (ref "R8") (pin "2") (pinfunction "2_2") (pintype "passive"))
    )
    (net (code "55") (name "Net-(U$9-3.GND)") (class "Default")
      (node (ref "U$10") (pin "1.POS") (pinfunction "1.POS_1.POS") (pintype "bidirectional"))
      (node (ref "U$10") (pin "2.POS") (pinfunction "2.POS_2.POS") (pintype "bidirectional"))
      (node (ref "U$9") (pin "3.NEG") (pinfunction "3.GND_3.NEG") (pintype "bidirectional"))
    )
    (net (code "56") (name "unconnected-(PW_SW-1_A-Pad5.IN1)") (class "Default")
      (node (ref "PW_SW") (pin "5.IN1") (pinfunction "1_A_5.IN1") (pintype "bidirectional"))
    )
    (net (code "57") (name "unconnected-(PW_SW-1_B-Pad6.IN1)") (class "Default")
      (node (ref "PW_SW") (pin "6.IN1") (pinfunction "1_B_6.IN1") (pintype "bidirectional"))
    )
    (net (code "58") (name "unconnected-(PW_SW-2_B-Pad4.IN2)") (class "Default")
      (node (ref "PW_SW") (pin "4.IN2") (pinfunction "2_B_4.IN2") (pintype "bidirectional"))
    )
    (net (code "59") (name "unconnected-(PW_SW-CB-Pad2.COMM)") (class "Default")
      (node (ref "PW_SW") (pin "2.COMM") (pinfunction "CB_2.COMM") (pintype "bidirectional"))
    )
    (net (code "60") (name "unconnected-(S1-Pad2)") (class "Default")
      (node (ref "S1") (pin "2") (pinfunction "2_2") (pintype "passive"))
    )
    (net (code "61") (name "unconnected-(S1-Pad4)") (class "Default")
      (node (ref "S1") (pin "4") (pinfunction "4_4") (pintype "passive"))
    )
    (net (code "62") (name "unconnected-(U$1-DIO1-Pad6)") (class "Default")
      (node (ref "U$1") (pin "6") (pinfunction "DIO1_6") (pintype "bidirectional"))
    )
    (net (code "63") (name "unconnected-(U$1-DIO2-Pad7)") (class "Default")
      (node (ref "U$1") (pin "7") (pinfunction "DIO2_7") (pintype "bidirectional"))
    )
    (net (code "64") (name "unconnected-(U$1-DIO3-Pad8)") (class "Default")
      (node (ref "U$1") (pin "8") (pinfunction "DIO3_8") (pintype "bidirectional"))
    )
    (net (code "65") (name "unconnected-(U$1-DIO4-Pad9)") (class "Default")
      (node (ref "U$1") (pin "9") (pinfunction "DIO4_9") (pintype "bidirectional"))
    )
    (net (code "66") (name "unconnected-(U$1-DIO5-Pad10)") (class "Default")
      (node (ref "U$1") (pin "10") (pinfunction "DIO5_10") (pintype "bidirectional"))
    )
    (net (code "67") (name "unconnected-(U$1-DIO6-Pad11)") (class "Default")
      (node (ref "U$1") (pin "11") (pinfunction "DIO6_11") (pintype "bidirectional"))
    )
    (net (code "68") (name "unconnected-(U$1-DIO7-Pad12)") (class "Default")
      (node (ref "U$1") (pin "12") (pinfunction "DIO7_12") (pintype "bidirectional"))
    )
    (net (code "69") (name "unconnected-(U$1-DIO8-Pad14)") (class "Default")
      (node (ref "U$1") (pin "14") (pinfunction "DIO8_14") (pintype "bidirectional"))
    )
    (net (code "70") (name "unconnected-(U$1-DIO9-Pad15)") (class "Default")
      (node (ref "U$1") (pin "15") (pinfunction "DIO9_15") (pintype "bidirectional"))
    )
    (net (code "71") (name "unconnected-(U$1-DIO10-Pad16)") (class "Default")
      (node (ref "U$1") (pin "16") (pinfunction "DIO10_16") (pintype "bidirectional"))
    )
    (net (code "72") (name "unconnected-(U$1-DIO13-Pad19)") (class "Default")
      (node (ref "U$1") (pin "19") (pinfunction "DIO13_19") (pintype "bidirectional"))
    )
    (net (code "73") (name "unconnected-(U$1-DIO14-Pad20)") (class "Default")
      (node (ref "U$1") (pin "20") (pinfunction "DIO14_20") (pintype "bidirectional"))
    )
    (net (code "74") (name "unconnected-(U$1-DIO15-Pad21)") (class "Default")
      (node (ref "U$1") (pin "21") (pinfunction "DIO15_21") (pintype "bidirectional"))
    )
    (net (code "75") (name "unconnected-(U$1-DIO18-Pad28)") (class "Default")
      (node (ref "U$1") (pin "28") (pinfunction "DIO18_28") (pintype "bidirectional"))
    )
    (net (code "76") (name "unconnected-(U$1-DIO21-Pad31)") (class "Default")
      (node (ref "U$1") (pin "31") (pinfunction "DIO21_31") (pintype "bidirectional"))
    )
    (net (code "77") (name "unconnected-(U$1-DIO22-Pad32)") (class "Default")
      (node (ref "U$1") (pin "32") (pinfunction "DIO22_32") (pintype "bidirectional"))
    )
  )
)
